# HeaterCotrol.net
KiCad netlist of a schematic drawn in EAGLE
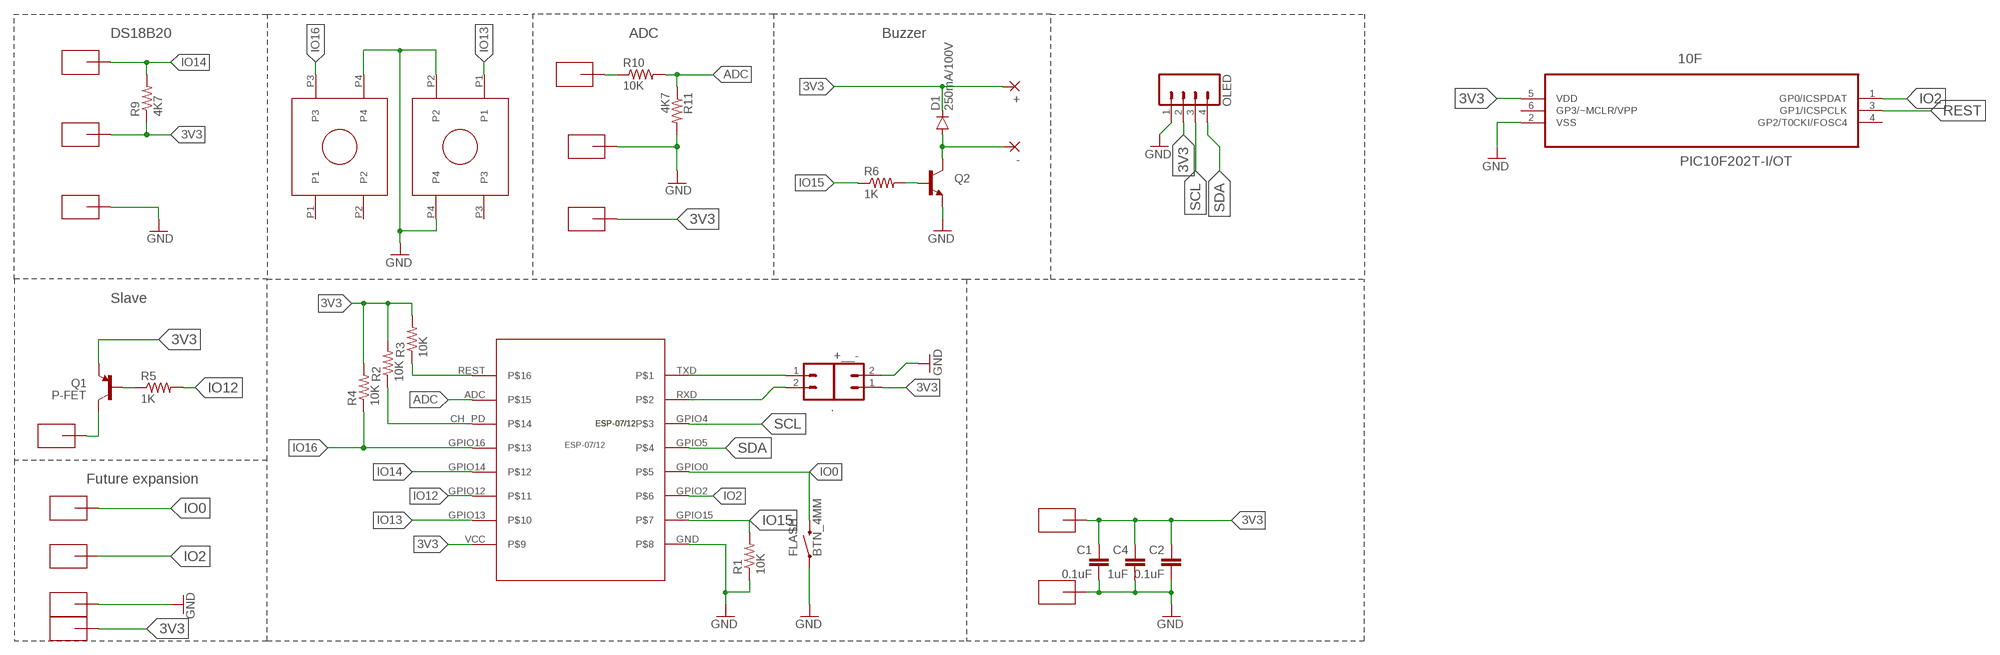
[diagram p0: schematic, sheet 1]

(export (version "E")
  (design (tool "Eeschema 10.0.6"))
  (components
    (comp (ref "+")
      (value "1,6/0,8")
      (footprint "eagle-import:1,6_0,8")
      (libsource (lib "eagle-import") (part "1,6/0,8"))
    )
    (comp (ref "+__-")
      (value "M02PTH")
      (footprint "eagle-import:1X02")
      (libsource (lib "eagle-import") (part "M02PTH"))
    )
    (comp (ref "-")
      (value "1,6/0,8")
      (footprint "eagle-import:1,6_0,8")
      (libsource (lib "eagle-import") (part "1,6/0,8"))
    )
    (comp (ref ".")
      (value "M02PTH")
      (footprint "eagle-import:1X02")
      (libsource (lib "eagle-import") (part "M02PTH"))
    )
    (comp (ref "10F")
      (value "PIC10F202T-I/OT")
      (footprint "eagle-import:SOT95P270X145-6N")
      (libsource (lib "eagle-import") (part "PIC10F202T-I/OT"))
    )
    (comp (ref "C1")
      (value "0.1uF")
      (footprint "eagle-import:0805-CAP")
      (libsource (lib "eagle-import") (part "CAP"))
    )
    (comp (ref "C2")
      (value "0.1uF")
      (footprint "eagle-import:0805-CAP")
      (libsource (lib "eagle-import") (part "CAP"))
    )
    (comp (ref "C4")
      (value "1uF")
      (footprint "eagle-import:0805-CAP")
      (libsource (lib "eagle-import") (part "CAP"))
    )
    (comp (ref "D1")
      (value "250mA/100V")
      (footprint "eagle-import:SOD-323")
      (libsource (lib "eagle-import") (part "DIODEBAS16"))
    )
    (comp (ref "FLASH")
      (value "BTN_4MM")
      (footprint "eagle-import:BTN_4MM")
      (libsource (lib "eagle-import") (part "BTN_4MM"))
    )
    (comp (ref "LEFT")
      (value "OMROM_TH")
      (footprint "eagle-import:OMROM_TH")
      (libsource (lib "eagle-import") (part "OMROM_TH"))
    )
    (comp (ref "OLED")
      (value "M04PTH")
      (footprint "eagle-import:1X04")
      (libsource (lib "eagle-import") (part "M04PTH"))
    )
    (comp (ref "Q1")
      (value "P-FET")
      (footprint "eagle-import:SOT23-3")
      (libsource (lib "eagle-import") (part "TRANSISTOR_PNPSMD"))
    )
    (comp (ref "Q2")
      (value "TRANSISTOR_NPNSOT23-3")
      (footprint "eagle-import:SOT23-3")
      (libsource (lib "eagle-import") (part "TRANSISTOR_NPNSOT23-3"))
    )
    (comp (ref "R1")
      (value "10K")
      (footprint "eagle-import:0805")
      (libsource (lib "eagle-import") (part "RESISTOR0805-RES"))
    )
    (comp (ref "R2")
      (value "10K")
      (footprint "eagle-import:0805")
      (libsource (lib "eagle-import") (part "RESISTOR0805-RES"))
    )
    (comp (ref "R3")
      (value "10K")
      (footprint "eagle-import:0805")
      (libsource (lib "eagle-import") (part "RESISTOR0805-RES"))
    )
    (comp (ref "R4")
      (value "10K")
      (footprint "eagle-import:0805")
      (libsource (lib "eagle-import") (part "RESISTOR0805-RES"))
    )
    (comp (ref "R5")
      (value "1K")
      (footprint "eagle-import:0805")
      (libsource (lib "eagle-import") (part "RESISTOR0805-RES"))
    )
    (comp (ref "R6")
      (value "1K")
      (footprint "eagle-import:0805")
      (libsource (lib "eagle-import") (part "RESISTOR0805-RES"))
    )
    (comp (ref "R9")
      (value "4K7")
      (footprint "eagle-import:0805")
      (libsource (lib "eagle-import") (part "RESISTOR0805-RES"))
    )
    (comp (ref "R10")
      (value "10K")
      (footprint "eagle-import:0805")
      (libsource (lib "eagle-import") (part "RESISTOR0805-RES"))
    )
    (comp (ref "R11")
      (value "4K7")
      (footprint "eagle-import:0805")
      (libsource (lib "eagle-import") (part "RESISTOR0805-RES"))
    )
    (comp (ref "RIGHT")
      (value "OMROM_TH")
      (footprint "eagle-import:OMROM_TH")
      (libsource (lib "eagle-import") (part "OMROM_TH"))
    )
    (comp (ref "U$1")
      (value "ESP-07/12")
      (footprint "eagle-import:ESP-07_12")
      (libsource (lib "eagle-import") (part "ESP-07/12"))
    )
    (comp (ref "U$2")
      (value "SMD-PAD1")
      (footprint "eagle-import:SMD-PAD1")
      (libsource (lib "eagle-import") (part "SMD-PAD1"))
    )
    (comp (ref "U$3")
      (value "SMD-PAD1")
      (footprint "eagle-import:SMD-PAD1")
      (libsource (lib "eagle-import") (part "SMD-PAD1"))
    )
    (comp (ref "U$4")
      (value "SMD-PAD1")
      (footprint "eagle-import:SMD-PAD1")
      (libsource (lib "eagle-import") (part "SMD-PAD1"))
    )
    (comp (ref "U$5")
      (value "SMD-PAD1")
      (footprint "eagle-import:SMD-PAD1")
      (libsource (lib "eagle-import") (part "SMD-PAD1"))
    )
    (comp (ref "U$6")
      (value "SMD-PAD1")
      (footprint "eagle-import:SMD-PAD1")
      (libsource (lib "eagle-import") (part "SMD-PAD1"))
    )
    (comp (ref "U$7")
      (value "SMD-PAD1")
      (footprint "eagle-import:SMD-PAD1")
      (libsource (lib "eagle-import") (part "SMD-PAD1"))
    )
    (comp (ref "U$8")
      (value "SMD-PAD1")
      (footprint "eagle-import:SMD-PAD1")
      (libsource (lib "eagle-import") (part "SMD-PAD1"))
    )
    (comp (ref "U$9")
      (value "SMD-PAD1")
      (footprint "eagle-import:SMD-PAD1")
      (libsource (lib "eagle-import") (part "SMD-PAD1"))
    )
    (comp (ref "U$10")
      (value "SMD-PAD1")
      (footprint "eagle-import:SMD-PAD1")
      (libsource (lib "eagle-import") (part "SMD-PAD1"))
    )
    (comp (ref "U$11")
      (value "SMD-PAD1")
      (footprint "eagle-import:SMD-PAD1")
      (libsource (lib "eagle-import") (part "SMD-PAD1"))
    )
    (comp (ref "U$12")
      (value "SMD-PAD1")
      (footprint "eagle-import:SMD-PAD1")
      (libsource (lib "eagle-import") (part "SMD-PAD1"))
    )
    (comp (ref "U$13")
      (value "SMD-PAD1")
      (footprint "eagle-import:SMD-PAD1")
      (libsource (lib "eagle-import") (part "SMD-PAD1"))
    )
    (comp (ref "U$14")
      (value "SMD-PAD1")
      (footprint "eagle-import:SMD-PAD1")
      (libsource (lib "eagle-import") (part "SMD-PAD1"))
    )
  )
  (nets
    (net (code "1") (name "3V3") (class "Default")
      (node (ref "+") (pin "1") (pinfunction "P_1") (pintype "passive"))
      (node (ref "+__-") (pin "1") (pinfunction "1_1") (pintype "passive"))
      (node (ref "10F") (pin "5") (pinfunction "VDD_5") (pintype "power_in"))
      (node (ref "C1") (pin "1") (pinfunction "1_1") (pintype "passive"))
      (node (ref "C2") (pin "1") (pinfunction "1_1") (pintype "passive"))
      (node (ref "C4") (pin "1") (pinfunction "1_1") (pintype "passive"))
      (node (ref "D1") (pin "C") (pinfunction "C_C") (pintype "passive"))
      (node (ref "OLED") (pin "2") (pinfunction "2_2") (pintype "passive"))
      (node (ref "Q1") (pin "2") (pinfunction "E_2") (pintype "passive"))
      (node (ref "R2") (pin "2") (pinfunction "2_2") (pintype "passive"))
      (node (ref "R3") (pin "2") (pinfunction "2_2") (pintype "passive"))
      (node (ref "R4") (pin "2") (pinfunction "2_2") (pintype "passive"))
      (node (ref "R9") (pin "1") (pinfunction "1_1") (pintype "passive"))
      (node (ref "U$1") (pin "VCC") (pinfunction "P$9_VCC") (pintype "bidirectional"))
      (node (ref "U$3") (pin ">NAME") (pinfunction "P$1_>NAME") (pintype "bidirectional"))
      (node (ref "U$5") (pin ">NAME") (pinfunction "P$1_>NAME") (pintype "bidirectional"))
      (node (ref "U$8") (pin ">NAME") (pinfunction "P$1_>NAME") (pintype "bidirectional"))
      (node (ref "U$9") (pin ">NAME") (pinfunction "P$1_>NAME") (pintype "bidirectional"))
    )
    (net (code "2") (name "ADC") (class "Default")
      (node (ref "R10") (pin "2") (pinfunction "2_2") (pintype "passive"))
      (node (ref "R11") (pin "1") (pinfunction "1_1") (pintype "passive"))
      (node (ref "U$1") (pin "ADC") (pinfunction "P$15_ADC") (pintype "bidirectional"))
    )
    (net (code "3") (name "GND") (class "Default")
      (node (ref "+__-") (pin "2") (pinfunction "2_2") (pintype "passive"))
      (node (ref "10F") (pin "2") (pinfunction "VSS_2") (pintype "power_in"))
      (node (ref "C1") (pin "2") (pinfunction "2_2") (pintype "passive"))
      (node (ref "C2") (pin "2") (pinfunction "2_2") (pintype "passive"))
      (node (ref "C4") (pin "2") (pinfunction "2_2") (pintype "passive"))
      (node (ref "FLASH") (pin "1") (pinfunction "1_1") (pintype "passive"))
      (node (ref "LEFT") (pin "P4") (pinfunction "P4_P4") (pintype "bidirectional"))
      (node (ref "OLED") (pin "1") (pinfunction "1_1") (pintype "passive"))
      (node (ref "Q2") (pin "2") (pinfunction "E_2") (pintype "passive"))
      (node (ref "R1") (pin "1") (pinfunction "1_1") (pintype "passive"))
      (node (ref "R11") (pin "2") (pinfunction "2_2") (pintype "passive"))
      (node (ref "RIGHT") (pin "P2") (pinfunction "P2_P2") (pintype "bidirectional"))
      (node (ref "RIGHT") (pin "P4") (pinfunction "P4_P4") (pintype "bidirectional"))
      (node (ref "U$1") (pin "GND") (pinfunction "P$8_GND") (pintype "bidirectional"))
      (node (ref "U$11") (pin ">NAME") (pinfunction "P$1_>NAME") (pintype "bidirectional"))
      (node (ref "U$13") (pin ">NAME") (pinfunction "P$1_>NAME") (pintype "bidirectional"))
      (node (ref "U$4") (pin ">NAME") (pinfunction "P$1_>NAME") (pintype "bidirectional"))
      (node (ref "U$6") (pin ">NAME") (pinfunction "P$1_>NAME") (pintype "bidirectional"))
    )
    (net (code "4") (name "IO0") (class "Default")
      (node (ref "FLASH") (pin "2") (pinfunction "2_2") (pintype "passive"))
      (node (ref "U$1") (pin "GPIO0") (pinfunction "P$5_GPIO0") (pintype "bidirectional"))
      (node (ref "U$14") (pin ">NAME") (pinfunction "P$1_>NAME") (pintype "bidirectional"))
    )
    (net (code "5") (name "IO2") (class "Default")
      (node (ref "10F") (pin "1") (pinfunction "GP0/ICSPDAT_1") (pintype "bidirectional"))
      (node (ref "U$1") (pin "GPIO2") (pinfunction "P$6_GPIO2") (pintype "bidirectional"))
      (node (ref "U$12") (pin ">NAME") (pinfunction "P$1_>NAME") (pintype "bidirectional"))
    )
    (net (code "6") (name "IO12") (class "Default")
      (node (ref "R5") (pin "2") (pinfunction "2_2") (pintype "passive"))
      (node (ref "U$1") (pin "GPIO12") (pinfunction "P$11_GPIO12") (pintype "bidirectional"))
    )
    (net (code "7") (name "IO13") (class "Default")
      (node (ref "RIGHT") (pin "P1") (pinfunction "P1_P1") (pintype "bidirectional"))
      (node (ref "U$1") (pin "GPIO13") (pinfunction "P$10_GPIO13") (pintype "bidirectional"))
    )
    (net (code "8") (name "IO14") (class "Default")
      (node (ref "R9") (pin "2") (pinfunction "2_2") (pintype "passive"))
      (node (ref "U$1") (pin "GPIO14") (pinfunction "P$12_GPIO14") (pintype "bidirectional"))
      (node (ref "U$10") (pin ">NAME") (pinfunction "P$1_>NAME") (pintype "bidirectional"))
    )
    (net (code "9") (name "IO15") (class "Default")
      (node (ref "R1") (pin "2") (pinfunction "2_2") (pintype "passive"))
      (node (ref "R6") (pin "1") (pinfunction "1_1") (pintype "passive"))
      (node (ref "U$1") (pin "GPIO15") (pinfunction "P$7_GPIO15") (pintype "bidirectional"))
    )
    (net (code "10") (name "IO16") (class "Default")
      (node (ref "LEFT") (pin "P3") (pinfunction "P3_P3") (pintype "bidirectional"))
      (node (ref "R4") (pin "1") (pinfunction "1_1") (pintype "passive"))
      (node (ref "U$1") (pin "GPIO16") (pinfunction "P$13_GPIO16") (pintype "bidirectional"))
    )
    (net (code "11") (name "Net-(--P)") (class "Default")
      (node (ref "-") (pin "1") (pinfunction "P_1") (pintype "passive"))
      (node (ref "D1") (pin "A") (pinfunction "A_A") (pintype "passive"))
      (node (ref "Q2") (pin "3") (pinfunction "C_3") (pintype "passive"))
    )
    (net (code "12") (name "Net-(Q1-B)") (class "Default")
      (node (ref "Q1") (pin "1") (pinfunction "B_1") (pintype "passive"))
      (node (ref "R5") (pin "1") (pinfunction "1_1") (pintype "passive"))
    )
    (net (code "13") (name "Net-(Q1-C)") (class "Default")
      (node (ref "Q1") (pin "3") (pinfunction "C_3") (pintype "passive"))
      (node (ref "U$2") (pin ">NAME") (pinfunction "P$1_>NAME") (pintype "bidirectional"))
    )
    (net (code "14") (name "Net-(Q2-B)") (class "Default")
      (node (ref "Q2") (pin "1") (pinfunction "B_1") (pintype "passive"))
      (node (ref "R6") (pin "2") (pinfunction "2_2") (pintype "passive"))
    )
    (net (code "15") (name "Net-(U$1-P$1)") (class "Default")
      (node (ref ".") (pin "1") (pinfunction "1_1") (pintype "passive"))
      (node (ref "U$1") (pin "TXD") (pinfunction "P$1_TXD") (pintype "bidirectional"))
    )
    (net (code "16") (name "Net-(U$1-P$2)") (class "Default")
      (node (ref ".") (pin "2") (pinfunction "2_2") (pintype "passive"))
      (node (ref "U$1") (pin "RXD") (pinfunction "P$2_RXD") (pintype "bidirectional"))
    )
    (net (code "17") (name "Net-(U$1-P$14)") (class "Default")
      (node (ref "R2") (pin "1") (pinfunction "1_1") (pintype "passive"))
      (node (ref "U$1") (pin "CH_PD") (pinfunction "P$14_CH_PD") (pintype "bidirectional"))
    )
    (net (code "18") (name "Net-(U$7-P$1)") (class "Default")
      (node (ref "R10") (pin "1") (pinfunction "1_1") (pintype "passive"))
      (node (ref "U$7") (pin ">NAME") (pinfunction "P$1_>NAME") (pintype "bidirectional"))
    )
    (net (code "19") (name "REST") (class "Default")
      (node (ref "10F") (pin "3") (pinfunction "GP1/ICSPCLK_3") (pintype "bidirectional"))
      (node (ref "R3") (pin "1") (pinfunction "1_1") (pintype "passive"))
      (node (ref "U$1") (pin "REST") (pinfunction "P$16_REST") (pintype "bidirectional"))
    )
    (net (code "20") (name "SCL") (class "Default")
      (node (ref "OLED") (pin "3") (pinfunction "3_3") (pintype "passive"))
      (node (ref "U$1") (pin "GPIO4") (pinfunction "P$3_GPIO4") (pintype "bidirectional"))
    )
    (net (code "21") (name "SDA") (class "Default")
      (node (ref "OLED") (pin "4") (pinfunction "4_4") (pintype "passive"))
      (node (ref "U$1") (pin "GPIO5") (pinfunction "P$4_GPIO5") (pintype "bidirectional"))
    )
    (net (code "22") (name "unconnected-(10F-GP2{slash}T0CKI{slash}FOSC4-Pad4)") (class "Default")
      (node (ref "10F") (pin "4") (pinfunction "GP2/T0CKI/FOSC4_4") (pintype "bidirectional"))
    )
    (net (code "23") (name "unconnected-(10F-GP3{slash}~{MCLR{slash}VPP}-Pad6)") (class "Default")
      (node (ref "10F") (pin "6") (pinfunction "GP3/~{MCLR/VPP}_6") (pintype "input"))
    )
    (net (code "24") (name "unconnected-(LEFT-PadP1)") (class "Default")
      (node (ref "LEFT") (pin "P1") (pinfunction "P1_P1") (pintype "bidirectional"))
    )
    (net (code "25") (name "unconnected-(LEFT-PadP2)") (class "Default")
      (node (ref "LEFT") (pin "P2") (pinfunction "P2_P2") (pintype "bidirectional"))
    )
    (net (code "26") (name "unconnected-(RIGHT-PadP3)") (class "Default")
      (node (ref "RIGHT") (pin "P3") (pinfunction "P3_P3") (pintype "bidirectional"))
    )
  )
)
